# SevenSegmentArrays.net
KiCad netlist of a schematic drawn in EAGLE
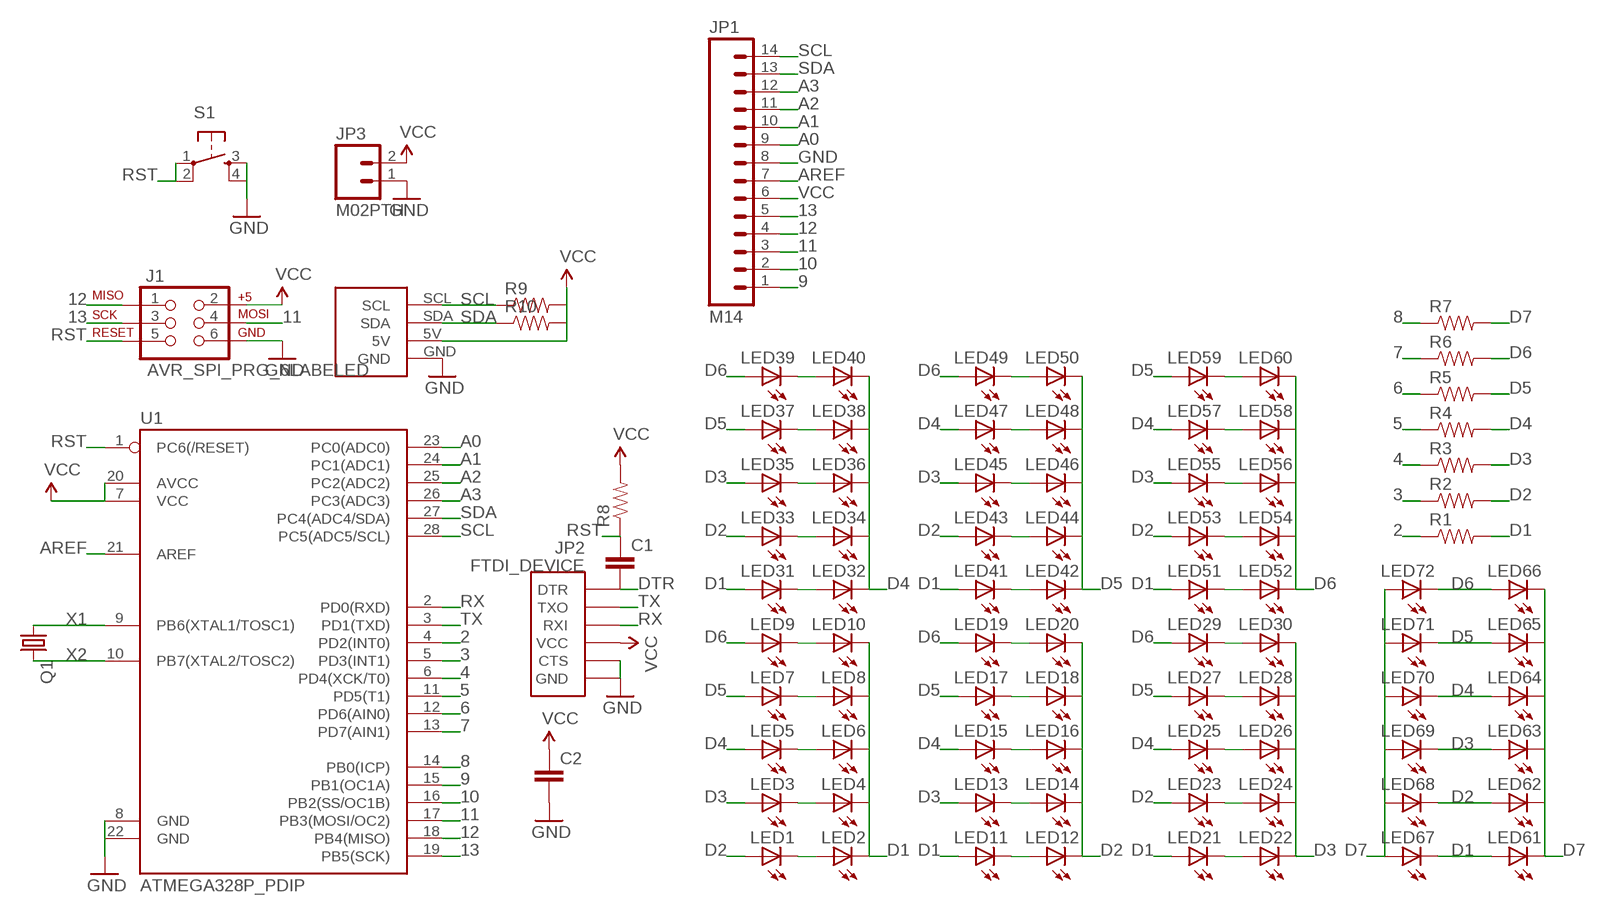
[diagram p0: schematic, sheet 1]

(export (version "E")
  (design (tool "Eeschema 10.0.6"))
  (components
    (comp (ref "C1")
      (value "CAPPTH")
      (footprint "eagle-import:CAP-PTH-SMALL")
      (libsource (lib "eagle-import") (part "CAPPTH"))
    )
    (comp (ref "C2")
      (value "CAPPTH")
      (footprint "eagle-import:CAP-PTH-SMALL")
      (libsource (lib "eagle-import") (part "CAPPTH"))
    )
    (comp (ref "J1")
      (value "AVR_SPI_PRG_6LABELED")
      (footprint "eagle-import:2X3-NS")
      (libsource (lib "eagle-import") (part "AVR_SPI_PRG_6LABELED"))
    )
    (comp (ref "JP1")
      (value "M14")
      (footprint "eagle-import:1X14")
      (libsource (lib "eagle-import") (part "M14"))
    )
    (comp (ref "JP2")
      (value "FTDI_DEVICE")
      (footprint "eagle-import:FTDI_DEVICE_SIDE")
      (libsource (lib "eagle-import") (part "FTDI_DEVICE"))
    )
    (comp (ref "JP3")
      (value "M02PTH")
      (footprint "eagle-import:1X02")
      (libsource (lib "eagle-import") (part "M02PTH"))
    )
    (comp (ref "LED1")
      (value "LEDRECT")
      (footprint "eagle-import:RECTANGLE_LED")
      (libsource (lib "eagle-import") (part "LEDRECT"))
    )
    (comp (ref "LED2")
      (value "LEDRECT")
      (footprint "eagle-import:RECTANGLE_LED")
      (libsource (lib "eagle-import") (part "LEDRECT"))
    )
    (comp (ref "LED3")
      (value "LEDRECT")
      (footprint "eagle-import:RECTANGLE_LED")
      (libsource (lib "eagle-import") (part "LEDRECT"))
    )
    (comp (ref "LED4")
      (value "LEDRECT")
      (footprint "eagle-import:RECTANGLE_LED")
      (libsource (lib "eagle-import") (part "LEDRECT"))
    )
    (comp (ref "LED5")
      (value "LEDRECT")
      (footprint "eagle-import:RECTANGLE_LED")
      (libsource (lib "eagle-import") (part "LEDRECT"))
    )
    (comp (ref "LED6")
      (value "LEDRECT")
      (footprint "eagle-import:RECTANGLE_LED")
      (libsource (lib "eagle-import") (part "LEDRECT"))
    )
    (comp (ref "LED7")
      (value "LEDRECT")
      (footprint "eagle-import:RECTANGLE_LED")
      (libsource (lib "eagle-import") (part "LEDRECT"))
    )
    (comp (ref "LED8")
      (value "LEDRECT")
      (footprint "eagle-import:RECTANGLE_LED")
      (libsource (lib "eagle-import") (part "LEDRECT"))
    )
    (comp (ref "LED9")
      (value "LEDRECT")
      (footprint "eagle-import:RECTANGLE_LED")
      (libsource (lib "eagle-import") (part "LEDRECT"))
    )
    (comp (ref "LED10")
      (value "LEDRECT")
      (footprint "eagle-import:RECTANGLE_LED")
      (libsource (lib "eagle-import") (part "LEDRECT"))
    )
    (comp (ref "LED11")
      (value "LEDRECT")
      (footprint "eagle-import:RECTANGLE_LED")
      (libsource (lib "eagle-import") (part "LEDRECT"))
    )
    (comp (ref "LED12")
      (value "LEDRECT")
      (footprint "eagle-import:RECTANGLE_LED")
      (libsource (lib "eagle-import") (part "LEDRECT"))
    )
    (comp (ref "LED13")
      (value "LEDRECT")
      (footprint "eagle-import:RECTANGLE_LED")
      (libsource (lib "eagle-import") (part "LEDRECT"))
    )
    (comp (ref "LED14")
      (value "LEDRECT")
      (footprint "eagle-import:RECTANGLE_LED")
      (libsource (lib "eagle-import") (part "LEDRECT"))
    )
    (comp (ref "LED15")
      (value "LEDRECT")
      (footprint "eagle-import:RECTANGLE_LED")
      (libsource (lib "eagle-import") (part "LEDRECT"))
    )
    (comp (ref "LED16")
      (value "LEDRECT")
      (footprint "eagle-import:RECTANGLE_LED")
      (libsource (lib "eagle-import") (part "LEDRECT"))
    )
    (comp (ref "LED17")
      (value "LEDRECT")
      (footprint "eagle-import:RECTANGLE_LED")
      (libsource (lib "eagle-import") (part "LEDRECT"))
    )
    (comp (ref "LED18")
      (value "LEDRECT")
      (footprint "eagle-import:RECTANGLE_LED")
      (libsource (lib "eagle-import") (part "LEDRECT"))
    )
    (comp (ref "LED19")
      (value "LEDRECT")
      (footprint "eagle-import:RECTANGLE_LED")
      (libsource (lib "eagle-import") (part "LEDRECT"))
    )
    (comp (ref "LED20")
      (value "LEDRECT")
      (footprint "eagle-import:RECTANGLE_LED")
      (libsource (lib "eagle-import") (part "LEDRECT"))
    )
    (comp (ref "LED21")
      (value "LEDRECT")
      (footprint "eagle-import:RECTANGLE_LED")
      (libsource (lib "eagle-import") (part "LEDRECT"))
    )
    (comp (ref "LED22")
      (value "LEDRECT")
      (footprint "eagle-import:RECTANGLE_LED")
      (libsource (lib "eagle-import") (part "LEDRECT"))
    )
    (comp (ref "LED23")
      (value "LEDRECT")
      (footprint "eagle-import:RECTANGLE_LED")
      (libsource (lib "eagle-import") (part "LEDRECT"))
    )
    (comp (ref "LED24")
      (value "LEDRECT")
      (footprint "eagle-import:RECTANGLE_LED")
      (libsource (lib "eagle-import") (part "LEDRECT"))
    )
    (comp (ref "LED25")
      (value "LEDRECT")
      (footprint "eagle-import:RECTANGLE_LED")
      (libsource (lib "eagle-import") (part "LEDRECT"))
    )
    (comp (ref "LED26")
      (value "LEDRECT")
      (footprint "eagle-import:RECTANGLE_LED")
      (libsource (lib "eagle-import") (part "LEDRECT"))
    )
    (comp (ref "LED27")
      (value "LEDRECT")
      (footprint "eagle-import:RECTANGLE_LED")
      (libsource (lib "eagle-import") (part "LEDRECT"))
    )
    (comp (ref "LED28")
      (value "LEDRECT")
      (footprint "eagle-import:RECTANGLE_LED")
      (libsource (lib "eagle-import") (part "LEDRECT"))
    )
    (comp (ref "LED29")
      (value "LEDRECT")
      (footprint "eagle-import:RECTANGLE_LED")
      (libsource (lib "eagle-import") (part "LEDRECT"))
    )
    (comp (ref "LED30")
      (value "LEDRECT")
      (footprint "eagle-import:RECTANGLE_LED")
      (libsource (lib "eagle-import") (part "LEDRECT"))
    )
    (comp (ref "LED31")
      (value "LEDRECT")
      (footprint "eagle-import:RECTANGLE_LED")
      (libsource (lib "eagle-import") (part "LEDRECT"))
    )
    (comp (ref "LED32")
      (value "LEDRECT")
      (footprint "eagle-import:RECTANGLE_LED")
      (libsource (lib "eagle-import") (part "LEDRECT"))
    )
    (comp (ref "LED33")
      (value "LEDRECT")
      (footprint "eagle-import:RECTANGLE_LED")
      (libsource (lib "eagle-import") (part "LEDRECT"))
    )
    (comp (ref "LED34")
      (value "LEDRECT")
      (footprint "eagle-import:RECTANGLE_LED")
      (libsource (lib "eagle-import") (part "LEDRECT"))
    )
    (comp (ref "LED35")
      (value "LEDRECT")
      (footprint "eagle-import:RECTANGLE_LED")
      (libsource (lib "eagle-import") (part "LEDRECT"))
    )
    (comp (ref "LED36")
      (value "LEDRECT")
      (footprint "eagle-import:RECTANGLE_LED")
      (libsource (lib "eagle-import") (part "LEDRECT"))
    )
    (comp (ref "LED37")
      (value "LEDRECT")
      (footprint "eagle-import:RECTANGLE_LED")
      (libsource (lib "eagle-import") (part "LEDRECT"))
    )
    (comp (ref "LED38")
      (value "LEDRECT")
      (footprint "eagle-import:RECTANGLE_LED")
      (libsource (lib "eagle-import") (part "LEDRECT"))
    )
    (comp (ref "LED39")
      (value "LEDRECT")
      (footprint "eagle-import:RECTANGLE_LED")
      (libsource (lib "eagle-import") (part "LEDRECT"))
    )
    (comp (ref "LED40")
      (value "LEDRECT")
      (footprint "eagle-import:RECTANGLE_LED")
      (libsource (lib "eagle-import") (part "LEDRECT"))
    )
    (comp (ref "LED41")
      (value "LEDRECT")
      (footprint "eagle-import:RECTANGLE_LED")
      (libsource (lib "eagle-import") (part "LEDRECT"))
    )
    (comp (ref "LED42")
      (value "LEDRECT")
      (footprint "eagle-import:RECTANGLE_LED")
      (libsource (lib "eagle-import") (part "LEDRECT"))
    )
    (comp (ref "LED43")
      (value "LEDRECT")
      (footprint "eagle-import:RECTANGLE_LED")
      (libsource (lib "eagle-import") (part "LEDRECT"))
    )
    (comp (ref "LED44")
      (value "LEDRECT")
      (footprint "eagle-import:RECTANGLE_LED")
      (libsource (lib "eagle-import") (part "LEDRECT"))
    )
    (comp (ref "LED45")
      (value "LEDRECT")
      (footprint "eagle-import:RECTANGLE_LED")
      (libsource (lib "eagle-import") (part "LEDRECT"))
    )
    (comp (ref "LED46")
      (value "LEDRECT")
      (footprint "eagle-import:RECTANGLE_LED")
      (libsource (lib "eagle-import") (part "LEDRECT"))
    )
    (comp (ref "LED47")
      (value "LEDRECT")
      (footprint "eagle-import:RECTANGLE_LED")
      (libsource (lib "eagle-import") (part "LEDRECT"))
    )
    (comp (ref "LED48")
      (value "LEDRECT")
      (footprint "eagle-import:RECTANGLE_LED")
      (libsource (lib "eagle-import") (part "LEDRECT"))
    )
    (comp (ref "LED49")
      (value "LEDRECT")
      (footprint "eagle-import:RECTANGLE_LED")
      (libsource (lib "eagle-import") (part "LEDRECT"))
    )
    (comp (ref "LED50")
      (value "LEDRECT")
      (footprint "eagle-import:RECTANGLE_LED")
      (libsource (lib "eagle-import") (part "LEDRECT"))
    )
    (comp (ref "LED51")
      (value "LEDRECT")
      (footprint "eagle-import:RECTANGLE_LED")
      (libsource (lib "eagle-import") (part "LEDRECT"))
    )
    (comp (ref "LED52")
      (value "LEDRECT")
      (footprint "eagle-import:RECTANGLE_LED")
      (libsource (lib "eagle-import") (part "LEDRECT"))
    )
    (comp (ref "LED53")
      (value "LEDRECT")
      (footprint "eagle-import:RECTANGLE_LED")
      (libsource (lib "eagle-import") (part "LEDRECT"))
    )
    (comp (ref "LED54")
      (value "LEDRECT")
      (footprint "eagle-import:RECTANGLE_LED")
      (libsource (lib "eagle-import") (part "LEDRECT"))
    )
    (comp (ref "LED55")
      (value "LEDRECT")
      (footprint "eagle-import:RECTANGLE_LED")
      (libsource (lib "eagle-import") (part "LEDRECT"))
    )
    (comp (ref "LED56")
      (value "LEDRECT")
      (footprint "eagle-import:RECTANGLE_LED")
      (libsource (lib "eagle-import") (part "LEDRECT"))
    )
    (comp (ref "LED57")
      (value "LED3MM")
      (footprint "eagle-import:LED3MM")
      (libsource (lib "eagle-import") (part "LED3MM"))
    )
    (comp (ref "LED58")
      (value "LED3MM")
      (footprint "eagle-import:LED3MM")
      (libsource (lib "eagle-import") (part "LED3MM"))
    )
    (comp (ref "LED59")
      (value "LED3MM")
      (footprint "eagle-import:LED3MM")
      (libsource (lib "eagle-import") (part "LED3MM"))
    )
    (comp (ref "LED60")
      (value "LED3MM")
      (footprint "eagle-import:LED3MM")
      (libsource (lib "eagle-import") (part "LED3MM"))
    )
    (comp (ref "LED61")
      (value "LED3MM")
      (footprint "eagle-import:LED3MM")
      (libsource (lib "eagle-import") (part "LED3MM"))
    )
    (comp (ref "LED62")
      (value "LED3MM")
      (footprint "eagle-import:LED3MM")
      (libsource (lib "eagle-import") (part "LED3MM"))
    )
    (comp (ref "LED63")
      (value "LED3MM")
      (footprint "eagle-import:LED3MM")
      (libsource (lib "eagle-import") (part "LED3MM"))
    )
    (comp (ref "LED64")
      (value "LED3MM")
      (footprint "eagle-import:LED3MM")
      (libsource (lib "eagle-import") (part "LED3MM"))
    )
    (comp (ref "LED65")
      (value "LED3MM")
      (footprint "eagle-import:LED3MM")
      (libsource (lib "eagle-import") (part "LED3MM"))
    )
    (comp (ref "LED66")
      (value "LED3MM")
      (footprint "eagle-import:LED3MM")
      (libsource (lib "eagle-import") (part "LED3MM"))
    )
    (comp (ref "LED67")
      (value "LED3MM")
      (footprint "eagle-import:LED3MM")
      (libsource (lib "eagle-import") (part "LED3MM"))
    )
    (comp (ref "LED68")
      (value "LED3MM")
      (footprint "eagle-import:LED3MM")
      (libsource (lib "eagle-import") (part "LED3MM"))
    )
    (comp (ref "LED69")
      (value "LED3MM")
      (footprint "eagle-import:LED3MM")
      (libsource (lib "eagle-import") (part "LED3MM"))
    )
    (comp (ref "LED70")
      (value "LED3MM")
      (footprint "eagle-import:LED3MM")
      (libsource (lib "eagle-import") (part "LED3MM"))
    )
    (comp (ref "LED71")
      (value "LED3MM")
      (footprint "eagle-import:LED3MM")
      (libsource (lib "eagle-import") (part "LED3MM"))
    )
    (comp (ref "LED72")
      (value "LED3MM")
      (footprint "eagle-import:LED3MM")
      (libsource (lib "eagle-import") (part "LED3MM"))
    )
    (comp (ref "Q1")
      (value "CRYSTALTC38H")
      (footprint "eagle-import:TC38H")
      (libsource (lib "eagle-import") (part "CRYSTALTC38H"))
    )
    (comp (ref "R1")
      (value "RESISTORAXIAL-0.3")
      (footprint "eagle-import:AXIAL-0.3")
      (libsource (lib "eagle-import") (part "RESISTORAXIAL-0.3"))
    )
    (comp (ref "R2")
      (value "RESISTORAXIAL-0.3")
      (footprint "eagle-import:AXIAL-0.3")
      (libsource (lib "eagle-import") (part "RESISTORAXIAL-0.3"))
    )
    (comp (ref "R3")
      (value "RESISTORAXIAL-0.3")
      (footprint "eagle-import:AXIAL-0.3")
      (libsource (lib "eagle-import") (part "RESISTORAXIAL-0.3"))
    )
    (comp (ref "R4")
      (value "RESISTORAXIAL-0.3")
      (footprint "eagle-import:AXIAL-0.3")
      (libsource (lib "eagle-import") (part "RESISTORAXIAL-0.3"))
    )
    (comp (ref "R5")
      (value "RESISTORAXIAL-0.3")
      (footprint "eagle-import:AXIAL-0.3")
      (libsource (lib "eagle-import") (part "RESISTORAXIAL-0.3"))
    )
    (comp (ref "R6")
      (value "RESISTORAXIAL-0.3")
      (footprint "eagle-import:AXIAL-0.3")
      (libsource (lib "eagle-import") (part "RESISTORAXIAL-0.3"))
    )
    (comp (ref "R7")
      (value "RESISTORAXIAL-0.3")
      (footprint "eagle-import:AXIAL-0.3")
      (libsource (lib "eagle-import") (part "RESISTORAXIAL-0.3"))
    )
    (comp (ref "R8")
      (value "RESISTORAXIAL-0.3")
      (footprint "eagle-import:AXIAL-0.3")
      (libsource (lib "eagle-import") (part "RESISTORAXIAL-0.3"))
    )
    (comp (ref "R9")
      (value "RESISTORAXIAL-0.3")
      (footprint "eagle-import:AXIAL-0.3")
      (libsource (lib "eagle-import") (part "RESISTORAXIAL-0.3"))
    )
    (comp (ref "R10")
      (value "RESISTORAXIAL-0.3")
      (footprint "eagle-import:AXIAL-0.3")
      (libsource (lib "eagle-import") (part "RESISTORAXIAL-0.3"))
    )
    (comp (ref "S1")
      (value "TAC_SWITCHPTH")
      (footprint "eagle-import:TACTILE-PTH")
      (libsource (lib "eagle-import") (part "TAC_SWITCHPTH"))
    )
    (comp (ref "U$1")
      (value "I2C")
      (footprint "eagle-import:I2C")
      (libsource (lib "eagle-import") (part "I2C"))
    )
    (comp (ref "U1")
      (value "ATMEGA328P_PDIP")
      (footprint "eagle-import:DIL28-3")
      (libsource (lib "eagle-import") (part "ATMEGA328P_PDIP"))
    )
  )
  (nets
    (net (code "1") (name "/2") (class "Default")
      (node (ref "R1") (pin "P$1") (pinfunction "1_P$1") (pintype "passive"))
      (node (ref "U1") (pin "4") (pinfunction "PD2(INT0)_4") (pintype "bidirectional"))
    )
    (net (code "2") (name "/3") (class "Default")
      (node (ref "R2") (pin "P$1") (pinfunction "1_P$1") (pintype "passive"))
      (node (ref "U1") (pin "5") (pinfunction "PD3(INT1)_5") (pintype "bidirectional"))
    )
    (net (code "3") (name "/4") (class "Default")
      (node (ref "R3") (pin "P$1") (pinfunction "1_P$1") (pintype "passive"))
      (node (ref "U1") (pin "6") (pinfunction "PD4(XCK/T0)_6") (pintype "bidirectional"))
    )
    (net (code "4") (name "/5") (class "Default")
      (node (ref "R4") (pin "P$1") (pinfunction "1_P$1") (pintype "passive"))
      (node (ref "U1") (pin "11") (pinfunction "PD5(T1)_11") (pintype "bidirectional"))
    )
    (net (code "5") (name "/6") (class "Default")
      (node (ref "R5") (pin "P$1") (pinfunction "1_P$1") (pintype "passive"))
      (node (ref "U1") (pin "12") (pinfunction "PD6(AIN0)_12") (pintype "bidirectional"))
    )
    (net (code "6") (name "/7") (class "Default")
      (node (ref "R6") (pin "P$1") (pinfunction "1_P$1") (pintype "passive"))
      (node (ref "U1") (pin "13") (pinfunction "PD7(AIN1)_13") (pintype "bidirectional"))
    )
    (net (code "7") (name "/8") (class "Default")
      (node (ref "R7") (pin "P$1") (pinfunction "1_P$1") (pintype "passive"))
      (node (ref "U1") (pin "14") (pinfunction "PB0(ICP)_14") (pintype "bidirectional"))
    )
    (net (code "8") (name "/9") (class "Default")
      (node (ref "JP1") (pin "1") (pinfunction "1_1") (pintype "passive"))
      (node (ref "U1") (pin "15") (pinfunction "PB1(OC1A)_15") (pintype "bidirectional"))
    )
    (net (code "9") (name "/10") (class "Default")
      (node (ref "JP1") (pin "2") (pinfunction "2_2") (pintype "passive"))
      (node (ref "U1") (pin "16") (pinfunction "PB2(SS/OC1B)_16") (pintype "bidirectional"))
    )
    (net (code "10") (name "/11") (class "Default")
      (node (ref "J1") (pin "4") (pinfunction "4_4") (pintype "passive"))
      (node (ref "JP1") (pin "3") (pinfunction "3_3") (pintype "passive"))
      (node (ref "U1") (pin "17") (pinfunction "PB3(MOSI/OC2)_17") (pintype "bidirectional"))
    )
    (net (code "11") (name "/12") (class "Default")
      (node (ref "J1") (pin "1") (pinfunction "1_1") (pintype "passive"))
      (node (ref "JP1") (pin "4") (pinfunction "4_4") (pintype "passive"))
      (node (ref "U1") (pin "18") (pinfunction "PB4(MISO)_18") (pintype "bidirectional"))
    )
    (net (code "12") (name "/13") (class "Default")
      (node (ref "J1") (pin "3") (pinfunction "3_3") (pintype "passive"))
      (node (ref "JP1") (pin "5") (pinfunction "5_5") (pintype "passive"))
      (node (ref "U1") (pin "19") (pinfunction "PB5(SCK)_19") (pintype "bidirectional"))
    )
    (net (code "13") (name "/A0") (class "Default")
      (node (ref "JP1") (pin "9") (pinfunction "9_9") (pintype "passive"))
      (node (ref "U1") (pin "23") (pinfunction "PC0(ADC0)_23") (pintype "bidirectional"))
    )
    (net (code "14") (name "/A1") (class "Default")
      (node (ref "JP1") (pin "10") (pinfunction "10_10") (pintype "passive"))
      (node (ref "U1") (pin "24") (pinfunction "PC1(ADC1)_24") (pintype "bidirectional"))
    )
    (net (code "15") (name "/A2") (class "Default")
      (node (ref "JP1") (pin "11") (pinfunction "11_11") (pintype "passive"))
      (node (ref "U1") (pin "25") (pinfunction "PC2(ADC2)_25") (pintype "bidirectional"))
    )
    (net (code "16") (name "/A3") (class "Default")
      (node (ref "JP1") (pin "12") (pinfunction "12_12") (pintype "passive"))
      (node (ref "U1") (pin "26") (pinfunction "PC3(ADC3)_26") (pintype "bidirectional"))
    )
    (net (code "17") (name "/AREF") (class "Default")
      (node (ref "JP1") (pin "7") (pinfunction "7_7") (pintype "passive"))
      (node (ref "U1") (pin "21") (pinfunction "AREF_21") (pintype "bidirectional"))
    )
    (net (code "18") (name "/D1") (class "Default")
      (node (ref "LED10") (pin "C") (pinfunction "C_C") (pintype "passive"))
      (node (ref "LED11") (pin "A") (pinfunction "A_A") (pintype "passive"))
      (node (ref "LED2") (pin "C") (pinfunction "C_C") (pintype "passive"))
      (node (ref "LED21") (pin "A") (pinfunction "A_A") (pintype "passive"))
      (node (ref "LED31") (pin "A") (pinfunction "A_A") (pintype "passive"))
      (node (ref "LED4") (pin "C") (pinfunction "C_C") (pintype "passive"))
      (node (ref "LED41") (pin "A") (pinfunction "A_A") (pintype "passive"))
      (node (ref "LED51") (pin "A") (pinfunction "A_A") (pintype "passive"))
      (node (ref "LED6") (pin "C") (pinfunction "C_C") (pintype "passive"))
      (node (ref "LED61") (pin "A") (pinfunction "A_A") (pintype "passive"))
      (node (ref "LED67") (pin "K") (pinfunction "C_K") (pintype "passive"))
      (node (ref "LED8") (pin "C") (pinfunction "C_C") (pintype "passive"))
      (node (ref "R1") (pin "P$2") (pinfunction "2_P$2") (pintype "passive"))
    )
    (net (code "19") (name "/D2") (class "Default")
      (node (ref "LED1") (pin "A") (pinfunction "A_A") (pintype "passive"))
      (node (ref "LED12") (pin "C") (pinfunction "C_C") (pintype "passive"))
      (node (ref "LED14") (pin "C") (pinfunction "C_C") (pintype "passive"))
      (node (ref "LED16") (pin "C") (pinfunction "C_C") (pintype "passive"))
      (node (ref "LED18") (pin "C") (pinfunction "C_C") (pintype "passive"))
      (node (ref "LED20") (pin "C") (pinfunction "C_C") (pintype "passive"))
      (node (ref "LED23") (pin "A") (pinfunction "A_A") (pintype "passive"))
      (node (ref "LED33") (pin "A") (pinfunction "A_A") (pintype "passive"))
      (node (ref "LED43") (pin "A") (pinfunction "A_A") (pintype "passive"))
      (node (ref "LED53") (pin "A") (pinfunction "A_A") (pintype "passive"))
      (node (ref "LED62") (pin "A") (pinfunction "A_A") (pintype "passive"))
      (node (ref "LED68") (pin "K") (pinfunction "C_K") (pintype "passive"))
      (node (ref "R2") (pin "P$2") (pinfunction "2_P$2") (pintype "passive"))
    )
    (net (code "20") (name "/D3") (class "Default")
      (node (ref "LED13") (pin "A") (pinfunction "A_A") (pintype "passive"))
      (node (ref "LED22") (pin "C") (pinfunction "C_C") (pintype "passive"))
      (node (ref "LED24") (pin "C") (pinfunction "C_C") (pintype "passive"))
      (node (ref "LED26") (pin "C") (pinfunction "C_C") (pintype "passive"))
      (node (ref "LED28") (pin "C") (pinfunction "C_C") (pintype "passive"))
      (node (ref "LED3") (pin "A") (pinfunction "A_A") (pintype "passive"))
      (node (ref "LED30") (pin "C") (pinfunction "C_C") (pintype "passive"))
      (node (ref "LED35") (pin "A") (pinfunction "A_A") (pintype "passive"))
      (node (ref "LED45") (pin "A") (pinfunction "A_A") (pintype "passive"))
      (node (ref "LED55") (pin "A") (pinfunction "A_A") (pintype "passive"))
      (node (ref "LED63") (pin "A") (pinfunction "A_A") (pintype "passive"))
      (node (ref "LED69") (pin "K") (pinfunction "C_K") (pintype "passive"))
      (node (ref "R3") (pin "P$2") (pinfunction "2_P$2") (pintype "passive"))
    )
    (net (code "21") (name "/D4") (class "Default")
      (node (ref "LED15") (pin "A") (pinfunction "A_A") (pintype "passive"))
      (node (ref "LED25") (pin "A") (pinfunction "A_A") (pintype "passive"))
      (node (ref "LED32") (pin "C") (pinfunction "C_C") (pintype "passive"))
      (node (ref "LED34") (pin "C") (pinfunction "C_C") (pintype "passive"))
      (node (ref "LED36") (pin "C") (pinfunction "C_C") (pintype "passive"))
      (node (ref "LED38") (pin "C") (pinfunction "C_C") (pintype "passive"))
      (node (ref "LED40") (pin "C") (pinfunction "C_C") (pintype "passive"))
      (node (ref "LED47") (pin "A") (pinfunction "A_A") (pintype "passive"))
      (node (ref "LED5") (pin "A") (pinfunction "A_A") (pintype "passive"))
      (node (ref "LED57") (pin "A") (pinfunction "A_A") (pintype "passive"))
      (node (ref "LED64") (pin "A") (pinfunction "A_A") (pintype "passive"))
      (node (ref "LED70") (pin "K") (pinfunction "C_K") (pintype "passive"))
      (node (ref "R4") (pin "P$2") (pinfunction "2_P$2") (pintype "passive"))
    )
    (net (code "22") (name "/D5") (class "Default")
      (node (ref "LED17") (pin "A") (pinfunction "A_A") (pintype "passive"))
      (node (ref "LED27") (pin "A") (pinfunction "A_A") (pintype "passive"))
      (node (ref "LED37") (pin "A") (pinfunction "A_A") (pintype "passive"))
      (node (ref "LED42") (pin "C") (pinfunction "C_C") (pintype "passive"))
      (node (ref "LED44") (pin "C") (pinfunction "C_C") (pintype "passive"))
      (node (ref "LED46") (pin "C") (pinfunction "C_C") (pintype "passive"))
      (node (ref "LED48") (pin "C") (pinfunction "C_C") (pintype "passive"))
      (node (ref "LED50") (pin "C") (pinfunction "C_C") (pintype "passive"))
      (node (ref "LED59") (pin "A") (pinfunction "A_A") (pintype "passive"))
      (node (ref "LED65") (pin "A") (pinfunction "A_A") (pintype "passive"))
      (node (ref "LED7") (pin "A") (pinfunction "A_A") (pintype "passive"))
      (node (ref "LED71") (pin "K") (pinfunction "C_K") (pintype "passive"))
      (node (ref "R5") (pin "P$2") (pinfunction "2_P$2") (pintype "passive"))
    )
    (net (code "23") (name "/D6") (class "Default")
      (node (ref "LED19") (pin "A") (pinfunction "A_A") (pintype "passive"))
      (node (ref "LED29") (pin "A") (pinfunction "A_A") (pintype "passive"))
      (node (ref "LED39") (pin "A") (pinfunction "A_A") (pintype "passive"))
      (node (ref "LED49") (pin "A") (pinfunction "A_A") (pintype "passive"))
      (node (ref "LED52") (pin "C") (pinfunction "C_C") (pintype "passive"))
      (node (ref "LED54") (pin "C") (pinfunction "C_C") (pintype "passive"))
      (node (ref "LED56") (pin "C") (pinfunction "C_C") (pintype "passive"))
      (node (ref "LED58") (pin "K") (pinfunction "C_K") (pintype "passive"))
      (node (ref "LED60") (pin "K") (pinfunction "C_K") (pintype "passive"))
      (node (ref "LED66") (pin "A") (pinfunction "A_A") (pintype "passive"))
      (node (ref "LED72") (pin "K") (pinfunction "C_K") (pintype "passive"))
      (node (ref "LED9") (pin "A") (pinfunction "A_A") (pintype "passive"))
      (node (ref "R6") (pin "P$2") (pinfunction "2_P$2") (pintype "passive"))
    )
    (net (code "24") (name "/D7") (class "Default")
      (node (ref "LED61") (pin "K") (pinfunction "C_K") (pintype "passive"))
      (node (ref "LED62") (pin "K") (pinfunction "C_K") (pintype "passive"))
      (node (ref "LED63") (pin "K") (pinfunction "C_K") (pintype "passive"))
      (node (ref "LED64") (pin "K") (pinfunction "C_K") (pintype "passive"))
      (node (ref "LED65") (pin "K") (pinfunction "C_K") (pintype "passive"))
      (node (ref "LED66") (pin "K") (pinfunction "C_K") (pintype "passive"))
      (node (ref "LED67") (pin "A") (pinfunction "A_A") (pintype "passive"))
      (node (ref "LED68") (pin "A") (pinfunction "A_A") (pintype "passive"))
      (node (ref "LED69") (pin "A") (pinfunction "A_A") (pintype "passive"))
      (node (ref "LED70") (pin "A") (pinfunction "A_A") (pintype "passive"))
      (node (ref "LED71") (pin "A") (pinfunction "A_A") (pintype "passive"))
      (node (ref "LED72") (pin "A") (pinfunction "A_A") (pintype "passive"))
      (node (ref "R7") (pin "P$2") (pinfunction "2_P$2") (pintype "passive"))
    )
    (net (code "25") (name "/DTR") (class "Default")
      (node (ref "C1") (pin "2") (pinfunction "2_2") (pintype "passive"))
      (node (ref "JP2") (pin "P$1") (pinfunction "DTR_P$1") (pintype "bidirectional"))
    )
    (net (code "26") (name "/RST") (class "Default")
      (node (ref "C1") (pin "1") (pinfunction "1_1") (pintype "passive"))
      (node (ref "J1") (pin "5") (pinfunction "5_5") (pintype "passive"))
      (node (ref "R8") (pin "P$1") (pinfunction "1_P$1") (pintype "passive"))
      (node (ref "S1") (pin "1") (pinfunction "1_1") (pintype "passive"))
      (node (ref "S1") (pin "2") (pinfunction "2_2") (pintype "passive"))
      (node (ref "U1") (pin "1") (pinfunction "PC6(/RESET)_1") (pintype "bidirectional"))
    )
    (net (code "27") (name "/RX") (class "Default")
      (node (ref "JP2") (pin "P$3") (pinfunction "RXI_P$3") (pintype "bidirectional"))
      (node (ref "U1") (pin "2") (pinfunction "PD0(RXD)_2") (pintype "bidirectional"))
    )
    (net (code "28") (name "/SCL") (class "Default")
      (node (ref "JP1") (pin "14") (pinfunction "14_14") (pintype "passive"))
      (node (ref "R9") (pin "P$1") (pinfunction "1_P$1") (pintype "passive"))
      (node (ref "U$1") (pin "SCL") (pinfunction "SCL_SCL") (pintype "bidirectional"))
      (node (ref "U1") (pin "28") (pinfunction "PC5(ADC5/SCL)_28") (pintype "bidirectional"))
    )
    (net (code "29") (name "/SDA") (class "Default")
      (node (ref "JP1") (pin "13") (pinfunction "13_13") (pintype "passive"))
      (node (ref "R10") (pin "P$1") (pinfunction "1_P$1") (pintype "passive"))
      (node (ref "U$1") (pin "SDA") (pinfunction "SDA_SDA") (pintype "bidirectional"))
      (node (ref "U1") (pin "27") (pinfunction "PC4(ADC4/SDA)_27") (pintype "bidirectional"))
    )
    (net (code "30") (name "/TX") (class "Default")
      (node (ref "JP2") (pin "P$2") (pinfunction "TXO_P$2") (pintype "bidirectional"))
      (node (ref "U1") (pin "3") (pinfunction "PD1(TXD)_3") (pintype "bidirectional"))
    )
    (net (code "31") (name "/X1") (class "Default")
      (node (ref "Q1") (pin "1") (pinfunction "1_1") (pintype "passive"))
      (node (ref "U1") (pin "9") (pinfunction "PB6(XTAL1/TOSC1)_9") (pintype "bidirectional"))
    )
    (net (code "32") (name "/X2") (class "Default")
      (node (ref "Q1") (pin "2") (pinfunction "2_2") (pintype "passive"))
      (node (ref "U1") (pin "10") (pinfunction "PB7(XTAL2/TOSC2)_10") (pintype "bidirectional"))
    )
    (net (code "33") (name "GND") (class "Default")
      (node (ref "C2") (pin "2") (pinfunction "2_2") (pintype "passive"))
      (node (ref "J1") (pin "6") (pinfunction "6_6") (pintype "passive"))
      (node (ref "JP1") (pin "8") (pinfunction "8_8") (pintype "passive"))
      (node (ref "JP2") (pin "P$5") (pinfunction "CTS_P$5") (pintype "bidirectional"))
      (node (ref "JP2") (pin "P$6") (pinfunction "GND_P$6") (pintype "bidirectional"))
      (node (ref "JP3") (pin "1") (pinfunction "1_1") (pintype "passive"))
      (node (ref "S1") (pin "3") (pinfunction "3_3") (pintype "passive"))
      (node (ref "S1") (pin "4") (pinfunction "4_4") (pintype "passive"))
      (node (ref "U$1") (pin "GND") (pinfunction "GND_GND") (pintype "bidirectional"))
      (node (ref "U1") (pin "22") (pinfunction "GND_22") (pintype "bidirectional"))
      (node (ref "U1") (pin "8") (pinfunction "GND_8") (pintype "bidirectional"))
    )
    (net (code "34") (name "Net-(LED1-PadC)") (class "Default")
      (node (ref "LED1") (pin "C") (pinfunction "C_C") (pintype "passive"))
      (node (ref "LED2") (pin "A") (pinfunction "A_A") (pintype "passive"))
    )
    (net (code "35") (name "Net-(LED3-PadC)") (class "Default")
      (node (ref "LED3") (pin "C") (pinfunction "C_C") (pintype "passive"))
      (node (ref "LED4") (pin "A") (pinfunction "A_A") (pintype "passive"))
    )
    (net (code "36") (name "Net-(LED5-PadC)") (class "Default")
      (node (ref "LED5") (pin "C") (pinfunction "C_C") (pintype "passive"))
      (node (ref "LED6") (pin "A") (pinfunction "A_A") (pintype "passive"))
    )
    (net (code "37") (name "Net-(LED7-PadC)") (class "Default")
      (node (ref "LED7") (pin "C") (pinfunction "C_C") (pintype "passive"))
      (node (ref "LED8") (pin "A") (pinfunction "A_A") (pintype "passive"))
    )
    (net (code "38") (name "Net-(LED10-PadA)") (class "Default")
      (node (ref "LED10") (pin "A") (pinfunction "A_A") (pintype "passive"))
      (node (ref "LED9") (pin "C") (pinfunction "C_C") (pintype "passive"))
    )
    (net (code "39") (name "Net-(LED11-PadC)") (class "Default")
      (node (ref "LED11") (pin "C") (pinfunction "C_C") (pintype "passive"))
      (node (ref "LED12") (pin "A") (pinfunction "A_A") (pintype "passive"))
    )
    (net (code "40") (name "Net-(LED13-PadC)") (class "Default")
      (node (ref "LED13") (pin "C") (pinfunction "C_C") (pintype "passive"))
      (node (ref "LED14") (pin "A") (pinfunction "A_A") (pintype "passive"))
    )
    (net (code "41") (name "Net-(LED15-PadC)") (class "Default")
      (node (ref "LED15") (pin "C") (pinfunction "C_C") (pintype "passive"))
      (node (ref "LED16") (pin "A") (pinfunction "A_A") (pintype "passive"))
    )
    (net (code "42") (name "Net-(LED17-PadC)") (class "Default")
      (node (ref "LED17") (pin "C") (pinfunction "C_C") (pintype "passive"))
      (node (ref "LED18") (pin "A") (pinfunction "A_A") (pintype "passive"))
    )
    (net (code "43") (name "Net-(LED19-PadC)") (class "Default")
      (node (ref "LED19") (pin "C") (pinfunction "C_C") (pintype "passive"))
      (node (ref "LED20") (pin "A") (pinfunction "A_A") (pintype "passive"))
    )
    (net (code "44") (name "Net-(LED21-PadC)") (class "Default")
      (node (ref "LED21") (pin "C") (pinfunction "C_C") (pintype "passive"))
      (node (ref "LED22") (pin "A") (pinfunction "A_A") (pintype "passive"))
    )
    (net (code "45") (name "Net-(LED23-PadC)") (class "Default")
      (node (ref "LED23") (pin "C") (pinfunction "C_C") (pintype "passive"))
      (node (ref "LED24") (pin "A") (pinfunction "A_A") (pintype "passive"))
    )
    (net (code "46") (name "Net-(LED25-PadC)") (class "Default")
      (node (ref "LED25") (pin "C") (pinfunction "C_C") (pintype "passive"))
      (node (ref "LED26") (pin "A") (pinfunction "A_A") (pintype "passive"))
    )
    (net (code "47") (name "Net-(LED27-PadC)") (class "Default")
      (node (ref "LED27") (pin "C") (pinfunction "C_C") (pintype "passive"))
      (node (ref "LED28") (pin "A") (pinfunction "A_A") (pintype "passive"))
    )
    (net (code "48") (name "Net-(LED29-PadC)") (class "Default")
      (node (ref "LED29") (pin "C") (pinfunction "C_C") (pintype "passive"))
      (node (ref "LED30") (pin "A") (pinfunction "A_A") (pintype "passive"))
    )
    (net (code "49") (name "Net-(LED31-PadC)") (class "Default")
      (node (ref "LED31") (pin "C") (pinfunction "C_C") (pintype "passive"))
      (node (ref "LED32") (pin "A") (pinfunction "A_A") (pintype "passive"))
    )
    (net (code "50") (name "Net-(LED33-PadC)") (class "Default")
      (node (ref "LED33") (pin "C") (pinfunction "C_C") (pintype "passive"))
      (node (ref "LED34") (pin "A") (pinfunction "A_A") (pintype "passive"))
    )
    (net (code "51") (name "Net-(LED35-PadC)") (class "Default")
      (node (ref "LED35") (pin "C") (pinfunction "C_C") (pintype "passive"))
      (node (ref "LED36") (pin "A") (pinfunction "A_A") (pintype "passive"))
    )
    (net (code "52") (name "Net-(LED37-PadC)") (class "Default")
      (node (ref "LED37") (pin "C") (pinfunction "C_C") (pintype "passive"))
      (node (ref "LED38") (pin "A") (pinfunction "A_A") (pintype "passive"))
    )
    (net (code "53") (name "Net-(LED39-PadC)") (class "Default")
      (node (ref "LED39") (pin "C") (pinfunction "C_C") (pintype "passive"))
      (node (ref "LED40") (pin "A") (pinfunction "A_A") (pintype "passive"))
    )
    (net (code "54") (name "Net-(LED41-PadC)") (class "Default")
      (node (ref "LED41") (pin "C") (pinfunction "C_C") (pintype "passive"))
      (node (ref "LED42") (pin "A") (pinfunction "A_A") (pintype "passive"))
    )
    (net (code "55") (name "Net-(LED43-PadC)") (class "Default")
      (node (ref "LED43") (pin "C") (pinfunction "C_C") (pintype "passive"))
      (node (ref "LED44") (pin "A") (pinfunction "A_A") (pintype "passive"))
    )
    (net (code "56") (name "Net-(LED45-PadC)") (class "Default")
      (node (ref "LED45") (pin "C") (pinfunction "C_C") (pintype "passive"))
      (node (ref "LED46") (pin "A") (pinfunction "A_A") (pintype "passive"))
    )
    (net (code "57") (name "Net-(LED47-PadC)") (class "Default")
      (node (ref "LED47") (pin "C") (pinfunction "C_C") (pintype "passive"))
      (node (ref "LED48") (pin "A") (pinfunction "A_A") (pintype "passive"))
    )
    (net (code "58") (name "Net-(LED49-PadC)") (class "Default")
      (node (ref "LED49") (pin "C") (pinfunction "C_C") (pintype "passive"))
      (node (ref "LED50") (pin "A") (pinfunction "A_A") (pintype "passive"))
    )
    (net (code "59") (name "Net-(LED51-PadC)") (class "Default")
      (node (ref "LED51") (pin "C") (pinfunction "C_C") (pintype "passive"))
      (node (ref "LED52") (pin "A") (pinfunction "A_A") (pintype "passive"))
    )
    (net (code "60") (name "Net-(LED53-PadC)") (class "Default")
      (node (ref "LED53") (pin "C") (pinfunction "C_C") (pintype "passive"))
      (node (ref "LED54") (pin "A") (pinfunction "A_A") (pintype "passive"))
    )
    (net (code "61") (name "Net-(LED55-PadC)") (class "Default")
      (node (ref "LED55") (pin "C") (pinfunction "C_C") (pintype "passive"))
      (node (ref "LED56") (pin "A") (pinfunction "A_A") (pintype "passive"))
    )
    (net (code "62") (name "Net-(LED57-C)") (class "Default")
      (node (ref "LED57") (pin "K") (pinfunction "C_K") (pintype "passive"))
      (node (ref "LED58") (pin "A") (pinfunction "A_A") (pintype "passive"))
    )
    (net (code "63") (name "Net-(LED59-C)") (class "Default")
      (node (ref "LED59") (pin "K") (pinfunction "C_K") (pintype "passive"))
      (node (ref "LED60") (pin "A") (pinfunction "A_A") (pintype "passive"))
    )
    (net (code "64") (name "VCC") (class "Default")
      (node (ref "C2") (pin "1") (pinfunction "1_1") (pintype "passive"))
      (node (ref "J1") (pin "2") (pinfunction "2_2") (pintype "passive"))
      (node (ref "JP1") (pin "6") (pinfunction "6_6") (pintype "passive"))
      (node (ref "JP2") (pin "P$4") (pinfunction "VCC_P$4") (pintype "bidirectional"))
      (node (ref "JP3") (pin "2") (pinfunction "2_2") (pintype "passive"))
      (node (ref "R10") (pin "P$2") (pinfunction "2_P$2") (pintype "passive"))
      (node (ref "R8") (pin "P$2") (pinfunction "2_P$2") (pintype "passive"))
      (node (ref "R9") (pin "P$2") (pinfunction "2_P$2") (pintype "passive"))
      (node (ref "U$1") (pin "5V") (pinfunction "5V_5V") (pintype "bidirectional"))
      (node (ref "U1") (pin "20") (pinfunction "AVCC_20") (pintype "bidirectional"))
      (node (ref "U1") (pin "7") (pinfunction "VCC_7") (pintype "bidirectional"))
    )
  )
)
